# AT_Guard_Simple_Memory.net
KiCad netlist of a schematic drawn in Altium Designer
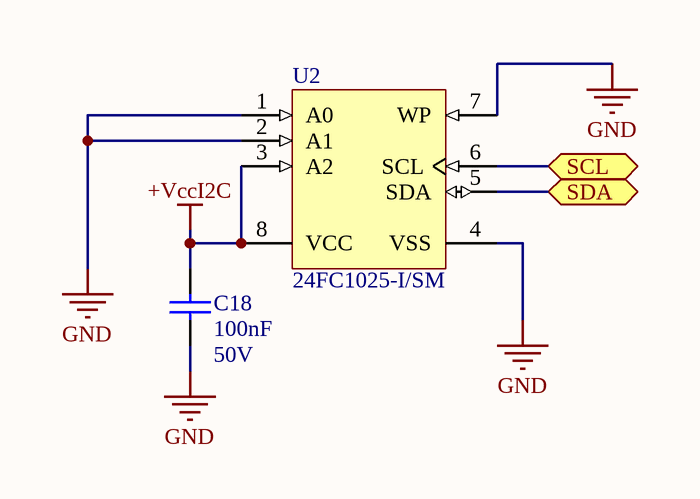
[diagram p0: AT Guard Simple Memory.SchDoc]

(export (version "E")
  (design (tool "Eeschema 10.0.6"))
  (components
    (comp (ref "C18")
      (value "100nF")
      (footprint "3-0603_L")
      (description "Capacitor")
      (fields
        (field (name "VOLTAGE") "50V")
        (field (name "Comment") "Cap")
        (field (name "PUBLISHER") "Altium Limited")
      )
      (libsource (lib "Erdem_05112012") (part "Cap"))
    )
    (comp (ref "U2")
      (value "24FC1025-I/SM")
      (footprint "SOIJ-SM8_N")
      (description "1 Mbit, 1MHz, 2.5V, I2C Serial EEPROM, 8-Pin SOIC 208mil, Industrial Temperature")
      (fields (field (name "PUBLISHER") "Altium Limited"))
      (libsource (lib "Erdem_05112012") (part "24FC1025-I/SM"))
    )
  )
  (nets
    (net (code "1") (name "+VccI2C") (class "Default")
      (node (ref "C18") (pin "2") (pinfunction "2_2") (pintype "passive"))
      (node (ref "U2") (pin "3") (pinfunction "A2_3") (pintype "input"))
      (node (ref "U2") (pin "8") (pinfunction "VCC_8") (pintype "power_in"))
    )
    (net (code "2") (name "/SCL") (class "Default")
      (node (ref "U2") (pin "6") (pinfunction "SCL_6") (pintype "input"))
    )
    (net (code "3") (name "/SDA") (class "Default")
      (node (ref "U2") (pin "5") (pinfunction "SDA_5") (pintype "bidirectional"))
    )
    (net (code "4") (name "GND") (class "Default")
      (node (ref "C18") (pin "1") (pinfunction "1_1") (pintype "passive"))
      (node (ref "U2") (pin "1") (pinfunction "A0_1") (pintype "input"))
      (node (ref "U2") (pin "2") (pinfunction "A1_2") (pintype "input"))
      (node (ref "U2") (pin "4") (pinfunction "VSS_4") (pintype "power_in"))
      (node (ref "U2") (pin "7") (pinfunction "WP_7") (pintype "input"))
    )
  )
)
